# POWER.net
KiCad netlist of a schematic drawn in Altium Designer
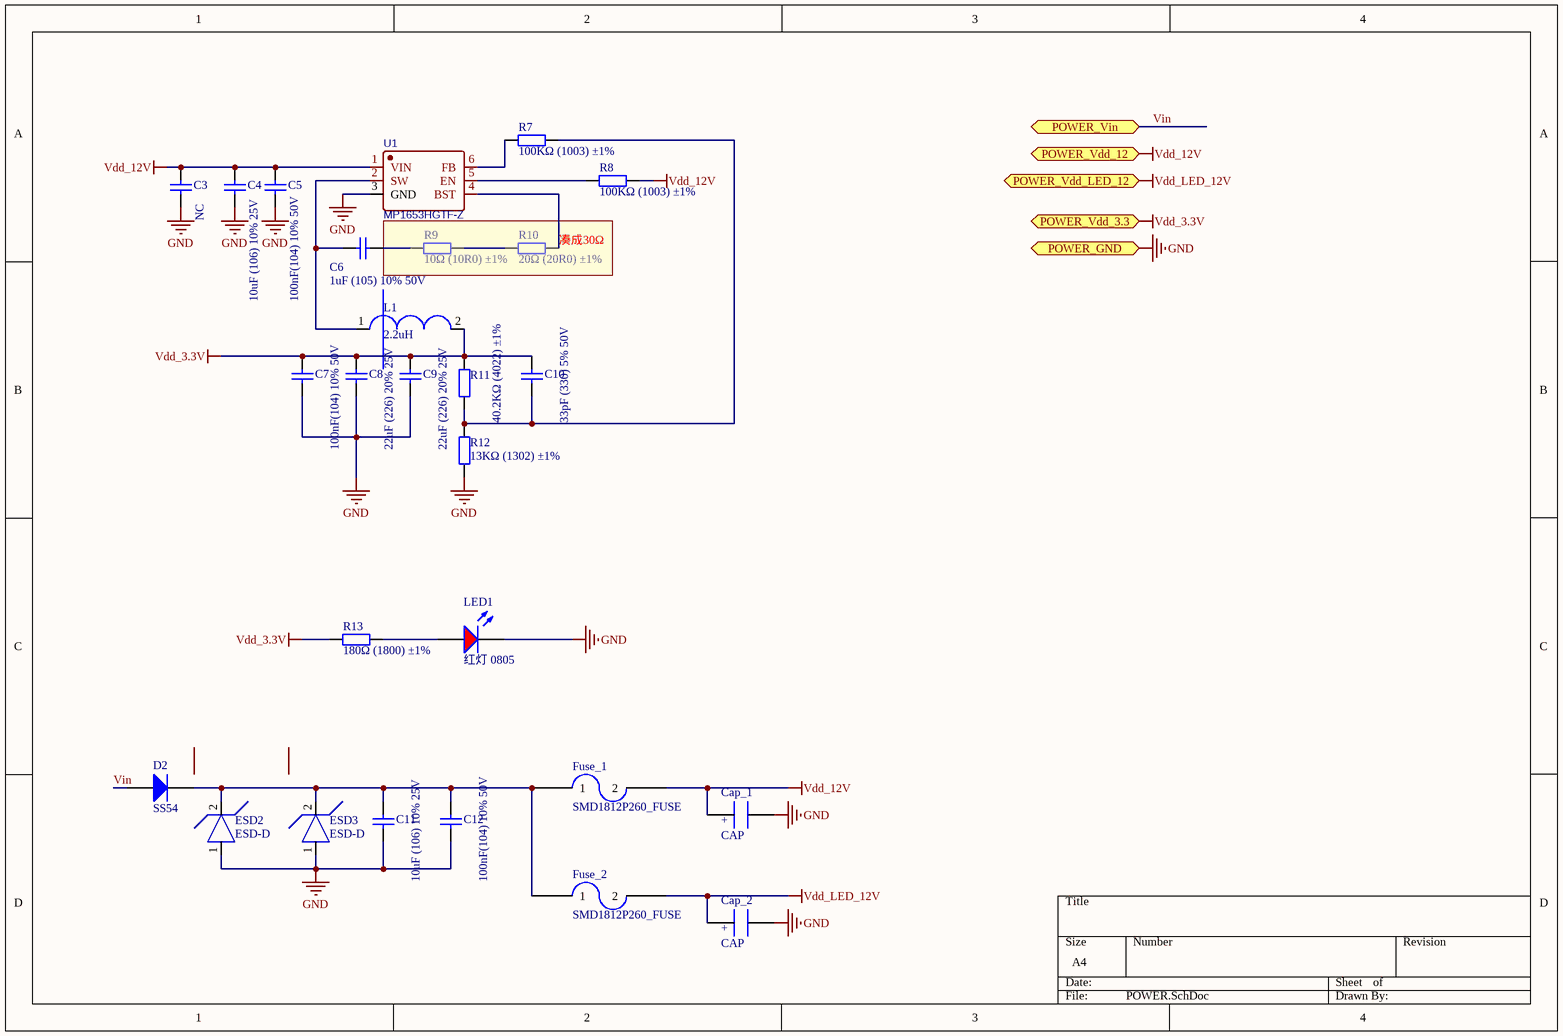
[diagram p0: POWER.SchDoc]

(export (version "E")
  (design (tool "Eeschema 10.0.6"))
  (components
    (comp (ref "C3")
      (value "NC")
      (footprint "0805_C")
      (description "贴片电容")
      (libsource (lib "Miscellaneous Devices LC") (part "0805 10uF (106) 10% 25V"))
    )
    (comp (ref "C4")
      (value "10uF (106) 10% 25V")
      (footprint "0805_C")
      (description "贴片电容")
      (libsource (lib "Miscellaneous Devices LC") (part "0805 10uF (106) 10% 25V"))
    )
    (comp (ref "C5")
      (value "100nF(104) 10% 50V")
      (footprint "0805_C")
      (description "贴片电容")
      (libsource (lib "Miscellaneous Devices LC") (part "0805 100nF(104) 10% 50V"))
    )
    (comp (ref "C6")
      (value "1uF (105) 10% 50V")
      (footprint "0805_C")
      (description "贴片电容")
      (libsource (lib "Miscellaneous Devices LC") (part "0805 1uF (105) 10% 50V"))
    )
    (comp (ref "C7")
      (value "100nF(104) 10% 50V")
      (footprint "0805_C")
      (description "贴片电容")
      (libsource (lib "Miscellaneous Devices LC") (part "0805 100nF(104) 10% 50V"))
    )
    (comp (ref "C8")
      (value "22uF (226) 20% 25V")
      (footprint "0805_C")
      (description "贴片电容")
      (libsource (lib "Miscellaneous Devices LC") (part "0805 22uF (226) 20% 25V"))
    )
    (comp (ref "C9")
      (value "22uF (226) 20% 25V")
      (footprint "0805_C")
      (description "贴片电容")
      (libsource (lib "Miscellaneous Devices LC") (part "0805 22uF (226) 20% 25V"))
    )
    (comp (ref "C10")
      (value "33pF (330) 5% 50V")
      (footprint "0805_C")
      (description "贴片电容")
      (libsource (lib "Miscellaneous Devices LC") (part "0805 33pF (330) 5% 50V"))
    )
    (comp (ref "C11")
      (value "10uF (106) 10% 25V")
      (footprint "0805_C")
      (description "贴片电容")
      (libsource (lib "Miscellaneous Devices LC") (part "0805 10uF (106) 10% 25V"))
    )
    (comp (ref "C12")
      (value "100nF(104) 10% 50V")
      (footprint "0805_C")
      (description "贴片电容")
      (libsource (lib "Miscellaneous Devices LC") (part "0805 100nF(104) 10% 50V"))
    )
    (comp (ref "Cap_1") (value "CAP") (footprint "8X12_CAP") (libsource (lib "mylib") (part "CAP")))
    (comp (ref "Cap_2") (value "CAP") (footprint "8X12_CAP") (libsource (lib "mylib") (part "CAP")))
    (comp (ref "D2")
      (value "SS54")
      (footprint "SMA(DO-214AC)_S1")
      (description "二极管")
      (libsource (lib "Miscellaneous Devices LC") (part "SMA(DO-214AC) SS54"))
    )
    (comp (ref "ESD2") (value "ESD-D") (footprint "SOD-523") (libsource (lib "mylib") (part "ESD-D")))
    (comp (ref "ESD3") (value "ESD-D") (footprint "SOD-523") (libsource (lib "mylib") (part "ESD-D")))
    (comp (ref "Fuse_1")
      (value "SMD1812P260_FUSE")
      (footprint "SMD1812P260")
      (libsource (lib "mylib") (part "SMD1812P260_FUSE"))
    )
    (comp (ref "Fuse_2")
      (value "SMD1812P260_FUSE")
      (footprint "SMD1812P260")
      (libsource (lib "mylib") (part "SMD1812P260_FUSE"))
    )
    (comp (ref "L1") (value "2.2uH") (footprint "L_4030") (libsource (lib "mylib") (part "33uH")))
    (comp (ref "LED1")
      (value "红灯 0805")
      (footprint "0805_LED_S1")
      (description "发光二极管")
      (libsource (lib "Miscellaneous Devices LC") (part "0805 红灯"))
    )
    (comp (ref "R7")
      (value "100KΩ (1003) ±1%")
      (footprint "0805_R")
      (description "贴片电阻")
      (libsource (lib "Miscellaneous Devices LC") (part "0805 100KΩ (1003) 1%"))
    )
    (comp (ref "R8")
      (value "100KΩ (1003) ±1%")
      (footprint "0805_R")
      (description "贴片电阻")
      (libsource (lib "Miscellaneous Devices LC") (part "0805 100KΩ (1003) 1%"))
    )
    (comp (ref "R9")
      (value "10Ω (10R0) ±1%")
      (footprint "0805_R")
      (description "贴片电阻")
      (libsource (lib "Miscellaneous Devices LC") (part "0805 10Ω (10R0) 1%"))
    )
    (comp (ref "R10")
      (value "20Ω (20R0) ±1%")
      (footprint "0805_R")
      (description "贴片电阻")
      (libsource (lib "Miscellaneous Devices LC") (part "0805 20Ω (20R0) 1%"))
    )
    (comp (ref "R11")
      (value "40.2KΩ (4022) ±1%")
      (footprint "0805_R")
      (description "贴片电阻")
      (libsource (lib "Miscellaneous Devices LC") (part "0805 40.2KΩ (4022) 1%"))
    )
    (comp (ref "R12")
      (value "13KΩ (1302) ±1%")
      (footprint "0805_R")
      (description "贴片电阻")
      (libsource (lib "Miscellaneous Devices LC") (part "0805 13KΩ (1302) 1%"))
    )
    (comp (ref "R13")
      (value "180Ω (1800) ±1%")
      (footprint "0805_R")
      (description "贴片电阻")
      (libsource (lib "Miscellaneous Devices LC") (part "0805 180Ω (1800) 1%"))
    )
    (comp (ref "U1")
      (value "MP1653HGTF-Z")
      (footprint "SOT563-6")
      (fields (field (name "BOM_SUPPLIER PART") "C132613"))
      (libsource (lib "mylib") (part "MP1653HGTF-Z"))
    )
  )
  (nets
    (net (code "1") (name "/Vin") (class "Default")
      (node (ref "D2") (pin "1") (pinfunction "A_1") (pintype "passive"))
    )
    (net (code "2") (name "GND") (class "Default")
      (node (ref "C11") (pin "1") (pinfunction "1_1") (pintype "passive"))
      (node (ref "C12") (pin "1") (pinfunction "1_1") (pintype "passive"))
      (node (ref "C3") (pin "1") (pinfunction "1_1") (pintype "passive"))
      (node (ref "C4") (pin "1") (pinfunction "1_1") (pintype "passive"))
      (node (ref "C5") (pin "1") (pinfunction "1_1") (pintype "passive"))
      (node (ref "C7") (pin "1") (pinfunction "1_1") (pintype "passive"))
      (node (ref "C8") (pin "1") (pinfunction "1_1") (pintype "passive"))
      (node (ref "C9") (pin "1") (pinfunction "1_1") (pintype "passive"))
      (node (ref "Cap_1") (pin "2") (pinfunction "2_2") (pintype "passive"))
      (node (ref "Cap_2") (pin "2") (pinfunction "2_2") (pintype "passive"))
      (node (ref "ESD2") (pin "1") (pinfunction "1_1") (pintype "passive"))
      (node (ref "ESD3") (pin "1") (pinfunction "1_1") (pintype "passive"))
      (node (ref "LED1") (pin "K") (pinfunction "K_K") (pintype "passive"))
      (node (ref "R12") (pin "1") (pinfunction "1_1") (pintype "passive"))
      (node (ref "U1") (pin "3") (pinfunction "GND_3") (pintype "passive"))
    )
    (net (code "3") (name "Net-(C6-Pad1)") (class "Default")
      (node (ref "C6") (pin "1") (pinfunction "1_1") (pintype "passive"))
      (node (ref "R9") (pin "2") (pinfunction "2_2") (pintype "passive"))
    )
    (net (code "4") (name "Net-(C10-Pad1)") (class "Default")
      (node (ref "C10") (pin "1") (pinfunction "1_1") (pintype "passive"))
      (node (ref "R11") (pin "2") (pinfunction "2_2") (pintype "passive"))
      (node (ref "R12") (pin "2") (pinfunction "2_2") (pintype "passive"))
      (node (ref "R7") (pin "2") (pinfunction "2_2") (pintype "passive"))
    )
    (net (code "5") (name "Net-(D2-K)") (class "Default")
      (node (ref "C11") (pin "2") (pinfunction "2_2") (pintype "passive"))
      (node (ref "C12") (pin "2") (pinfunction "2_2") (pintype "passive"))
      (node (ref "D2") (pin "2") (pinfunction "K_2") (pintype "passive"))
      (node (ref "ESD2") (pin "2") (pinfunction "2_2") (pintype "passive"))
      (node (ref "ESD3") (pin "2") (pinfunction "2_2") (pintype "passive"))
      (node (ref "Fuse_1") (pin "1") (pinfunction "1_1") (pintype "passive"))
      (node (ref "Fuse_2") (pin "1") (pinfunction "1_1") (pintype "passive"))
    )
    (net (code "6") (name "Net-(LED1-PadA)") (class "Default")
      (node (ref "LED1") (pin "A") (pinfunction "A_A") (pintype "passive"))
      (node (ref "R13") (pin "2") (pinfunction "2_2") (pintype "passive"))
    )
    (net (code "7") (name "Net-(R10-Pad2)") (class "Default")
      (node (ref "R10") (pin "2") (pinfunction "2_2") (pintype "passive"))
      (node (ref "R9") (pin "1") (pinfunction "1_1") (pintype "passive"))
    )
    (net (code "8") (name "Net-(U1-BST)") (class "Default")
      (node (ref "R10") (pin "1") (pinfunction "1_1") (pintype "passive"))
      (node (ref "U1") (pin "4") (pinfunction "BST_4") (pintype "passive"))
    )
    (net (code "9") (name "Net-(U1-EN)") (class "Default")
      (node (ref "R8") (pin "1") (pinfunction "1_1") (pintype "passive"))
      (node (ref "U1") (pin "5") (pinfunction "EN_5") (pintype "passive"))
    )
    (net (code "10") (name "Net-(U1-FB)") (class "Default")
      (node (ref "R7") (pin "1") (pinfunction "1_1") (pintype "passive"))
      (node (ref "U1") (pin "6") (pinfunction "FB_6") (pintype "passive"))
    )
    (net (code "11") (name "Net-(U1-SW)") (class "Default")
      (node (ref "C6") (pin "2") (pinfunction "2_2") (pintype "passive"))
      (node (ref "L1") (pin "1") (pinfunction "1_1") (pintype "passive"))
      (node (ref "U1") (pin "2") (pinfunction "SW_2") (pintype "passive"))
    )
    (net (code "12") (name "Vdd_3.3V") (class "Default")
      (node (ref "C10") (pin "2") (pinfunction "2_2") (pintype "passive"))
      (node (ref "C7") (pin "2") (pinfunction "2_2") (pintype "passive"))
      (node (ref "C8") (pin "2") (pinfunction "2_2") (pintype "passive"))
      (node (ref "C9") (pin "2") (pinfunction "2_2") (pintype "passive"))
      (node (ref "L1") (pin "2") (pinfunction "2_2") (pintype "passive"))
      (node (ref "R11") (pin "1") (pinfunction "1_1") (pintype "passive"))
      (node (ref "R13") (pin "1") (pinfunction "1_1") (pintype "passive"))
    )
    (net (code "13") (name "Vdd_12V") (class "Default")
      (node (ref "C3") (pin "2") (pinfunction "2_2") (pintype "passive"))
      (node (ref "C4") (pin "2") (pinfunction "2_2") (pintype "passive"))
      (node (ref "C5") (pin "2") (pinfunction "2_2") (pintype "passive"))
      (node (ref "Cap_1") (pin "1") (pinfunction "1_1") (pintype "passive"))
      (node (ref "Fuse_1") (pin "2") (pinfunction "2_2") (pintype "passive"))
      (node (ref "R8") (pin "2") (pinfunction "2_2") (pintype "passive"))
      (node (ref "U1") (pin "1") (pinfunction "VIN_1") (pintype "passive"))
    )
    (net (code "14") (name "Vdd_LED_12V") (class "Default")
      (node (ref "Cap_2") (pin "1") (pinfunction "1_1") (pintype "passive"))
      (node (ref "Fuse_2") (pin "2") (pinfunction "2_2") (pintype "passive"))
    )
  )
)
